# Snake.net
KiCad netlist of a schematic drawn in EAGLE
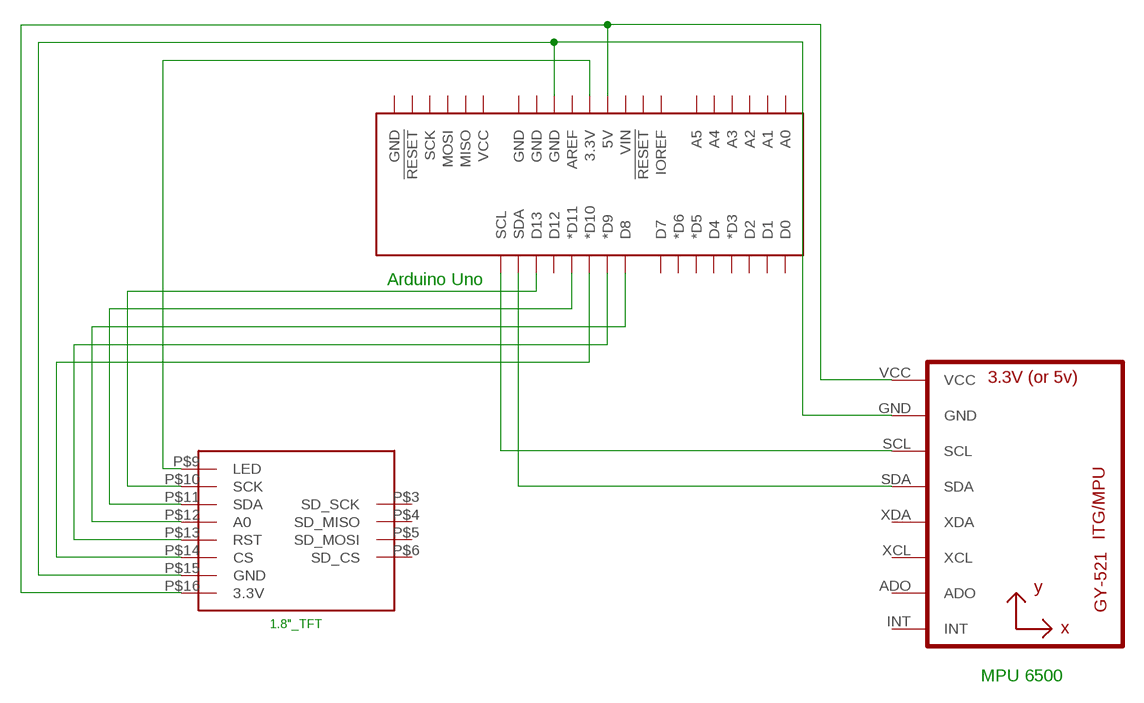
[diagram p0: schematic, sheet 1]

(export (version "E")
  (design (tool "Eeschema 10.0.6"))
  (components
    (comp (ref "B1")
      (value "ARDUINO_UNO_R3NO_HOLES")
      (footprint "eagle-import:ARDUINO_R3_NO_HOLES")
      (libsource (lib "eagle-import") (part "ARDUINO_UNO_R3NO_HOLES"))
    )
    (comp (ref "U$1")
      (value "1.8\"_TFT")
      (footprint "eagle-import:1.8__TFT")
      (libsource (lib "eagle-import") (part "1.8{dblquote}_TFT"))
    )
    (comp (ref "U1")
      (value "GY-521MPU6050")
      (footprint "eagle-import:GY-521")
      (libsource (lib "eagle-import") (part "GY-521MPU6050"))
    )
  )
  (nets
    (net (code "1") (name "Net-(B1-*D9)") (class "Default")
      (node (ref "B1") (pin "D9") (pinfunction "*D9_D9") (pintype "bidirectional"))
      (node (ref "U$1") (pin "P$13") (pinfunction "RST_P$13") (pintype "bidirectional"))
    )
    (net (code "2") (name "Net-(B1-*D10)") (class "Default")
      (node (ref "B1") (pin "D10") (pinfunction "*D10_D10") (pintype "bidirectional"))
      (node (ref "U$1") (pin "P$14") (pinfunction "CS_P$14") (pintype "bidirectional"))
    )
    (net (code "3") (name "Net-(B1-*D11)") (class "Default")
      (node (ref "B1") (pin "D11") (pinfunction "*D11_D11") (pintype "bidirectional"))
      (node (ref "U$1") (pin "P$11") (pinfunction "SDA_P$11") (pintype "bidirectional"))
    )
    (net (code "4") (name "Net-(B1-PadSCL)") (class "Default")
      (node (ref "B1") (pin "SCL") (pinfunction "SCL_SCL") (pintype "bidirectional"))
      (node (ref "U1") (pin "SCL") (pinfunction "SCL_SCL") (pintype "bidirectional"))
    )
    (net (code "5") (name "Net-(B1-PadSDA)") (class "Default")
      (node (ref "B1") (pin "SDA") (pinfunction "SDA_SDA") (pintype "bidirectional"))
      (node (ref "U1") (pin "SDA") (pinfunction "SDA_SDA") (pintype "bidirectional"))
    )
    (net (code "6") (name "Net-(U$1-3.3V)") (class "Default")
      (node (ref "B1") (pin "5V") (pinfunction "5V_5V") (pintype "bidirectional"))
      (node (ref "U$1") (pin "P$16") (pinfunction "3.3V_P$16") (pintype "bidirectional"))
      (node (ref "U1") (pin "VCC") (pinfunction "VCC_VCC") (pintype "bidirectional"))
    )
    (net (code "7") (name "Net-(U$1-A0)") (class "Default")
      (node (ref "B1") (pin "D8") (pinfunction "D8_D8") (pintype "bidirectional"))
      (node (ref "U$1") (pin "P$12") (pinfunction "A0_P$12") (pintype "bidirectional"))
    )
    (net (code "8") (name "Net-(U$1-GND)") (class "Default")
      (node (ref "B1") (pin "GND@4") (pinfunction "GND_GND@4") (pintype "bidirectional"))
      (node (ref "U$1") (pin "P$15") (pinfunction "GND_P$15") (pintype "bidirectional"))
      (node (ref "U1") (pin "GND") (pinfunction "GND_GND") (pintype "bidirectional"))
    )
    (net (code "9") (name "Net-(U$1-LED)") (class "Default")
      (node (ref "B1") (pin "3.3V") (pinfunction "3.3V_3.3V") (pintype "bidirectional"))
      (node (ref "U$1") (pin "P$9") (pinfunction "LED_P$9") (pintype "bidirectional"))
    )
    (net (code "10") (name "Net-(U$1-SCK)") (class "Default")
      (node (ref "B1") (pin "D13") (pinfunction "D13_D13") (pintype "bidirectional"))
      (node (ref "U$1") (pin "P$10") (pinfunction "SCK_P$10") (pintype "bidirectional"))
    )
    (net (code "11") (name "unconnected-(B1-*D3-PadD3)") (class "Default")
      (node (ref "B1") (pin "D3") (pinfunction "*D3_D3") (pintype "bidirectional"))
    )
    (net (code "12") (name "unconnected-(B1-*D5-PadD5)") (class "Default")
      (node (ref "B1") (pin "D5") (pinfunction "*D5_D5") (pintype "bidirectional"))
    )
    (net (code "13") (name "unconnected-(B1-*D6-PadD6)") (class "Default")
      (node (ref "B1") (pin "D6") (pinfunction "*D6_D6") (pintype "bidirectional"))
    )
    (net (code "14") (name "unconnected-(B1-GND-PadGND@1)") (class "Default")
      (node (ref "B1") (pin "GND@1") (pinfunction "GND_GND@1") (pintype "bidirectional"))
    )
    (net (code "15") (name "unconnected-(B1-GND-PadGND@2)") (class "Default")
      (node (ref "B1") (pin "GND@2") (pinfunction "GND_GND@2") (pintype "bidirectional"))
    )
    (net (code "16") (name "unconnected-(B1-GND-PadGND@3)") (class "Default")
      (node (ref "B1") (pin "GND@3") (pinfunction "GND_GND@3") (pintype "bidirectional"))
    )
    (net (code "17") (name "unconnected-(B1-PadA0)") (class "Default")
      (node (ref "B1") (pin "A0") (pinfunction "A0_A0") (pintype "bidirectional"))
    )
    (net (code "18") (name "unconnected-(B1-PadA1)") (class "Default")
      (node (ref "B1") (pin "A1") (pinfunction "A1_A1") (pintype "bidirectional"))
    )
    (net (code "19") (name "unconnected-(B1-PadA2)") (class "Default")
      (node (ref "B1") (pin "A2") (pinfunction "A2_A2") (pintype "bidirectional"))
    )
    (net (code "20") (name "unconnected-(B1-PadA3)") (class "Default")
      (node (ref "B1") (pin "A3") (pinfunction "A3_A3") (pintype "bidirectional"))
    )
    (net (code "21") (name "unconnected-(B1-PadA4)") (class "Default")
      (node (ref "B1") (pin "A4") (pinfunction "A4_A4") (pintype "bidirectional"))
    )
    (net (code "22") (name "unconnected-(B1-PadA5)") (class "Default")
      (node (ref "B1") (pin "A5") (pinfunction "A5_A5") (pintype "bidirectional"))
    )
    (net (code "23") (name "unconnected-(B1-PadAREF)") (class "Default")
      (node (ref "B1") (pin "AREF") (pinfunction "AREF_AREF") (pintype "bidirectional"))
    )
    (net (code "24") (name "unconnected-(B1-PadD0)") (class "Default")
      (node (ref "B1") (pin "D0") (pinfunction "D0_D0") (pintype "bidirectional"))
    )
    (net (code "25") (name "unconnected-(B1-PadD1)") (class "Default")
      (node (ref "B1") (pin "D1") (pinfunction "D1_D1") (pintype "bidirectional"))
    )
    (net (code "26") (name "unconnected-(B1-PadD2)") (class "Default")
      (node (ref "B1") (pin "D2") (pinfunction "D2_D2") (pintype "bidirectional"))
    )
    (net (code "27") (name "unconnected-(B1-PadD4)") (class "Default")
      (node (ref "B1") (pin "D4") (pinfunction "D4_D4") (pintype "bidirectional"))
    )
    (net (code "28") (name "unconnected-(B1-PadD7)") (class "Default")
      (node (ref "B1") (pin "D7") (pinfunction "D7_D7") (pintype "bidirectional"))
    )
    (net (code "29") (name "unconnected-(B1-PadD12)") (class "Default")
      (node (ref "B1") (pin "D12") (pinfunction "D12_D12") (pintype "bidirectional"))
    )
    (net (code "30") (name "unconnected-(B1-PadIOREF)") (class "Default")
      (node (ref "B1") (pin "IOREF") (pinfunction "IOREF_IOREF") (pintype "bidirectional"))
    )
    (net (code "31") (name "unconnected-(B1-PadMISO)") (class "Default")
      (node (ref "B1") (pin "MISO") (pinfunction "MISO_MISO") (pintype "bidirectional"))
    )
    (net (code "32") (name "unconnected-(B1-PadMOSI)") (class "Default")
      (node (ref "B1") (pin "MOSI") (pinfunction "MOSI_MOSI") (pintype "bidirectional"))
    )
    (net (code "33") (name "unconnected-(B1-PadSCK)") (class "Default")
      (node (ref "B1") (pin "SCK") (pinfunction "SCK_SCK") (pintype "bidirectional"))
    )
    (net (code "34") (name "unconnected-(B1-PadVCC)") (class "Default")
      (node (ref "B1") (pin "VCC") (pinfunction "VCC_VCC") (pintype "bidirectional"))
    )
    (net (code "35") (name "unconnected-(B1-PadVIN)") (class "Default")
      (node (ref "B1") (pin "VIN") (pinfunction "VIN_VIN") (pintype "bidirectional"))
    )
    (net (code "36") (name "unconnected-(B1-~{RESET}-PadRESET@1)") (class "Default")
      (node (ref "B1") (pin "RESET@1") (pinfunction "~{RESET}_RESET@1") (pintype "bidirectional"))
    )
    (net (code "37") (name "unconnected-(B1-~{RESET}-PadRESET@2)") (class "Default")
      (node (ref "B1") (pin "RESET@2") (pinfunction "~{RESET}_RESET@2") (pintype "bidirectional"))
    )
    (net (code "38") (name "unconnected-(U$1-SD_CS-PadP$6)") (class "Default")
      (node (ref "U$1") (pin "P$6") (pinfunction "SD_CS_P$6") (pintype "bidirectional"))
    )
    (net (code "39") (name "unconnected-(U$1-SD_MISO-PadP$4)") (class "Default")
      (node (ref "U$1") (pin "P$4") (pinfunction "SD_MISO_P$4") (pintype "bidirectional"))
    )
    (net (code "40") (name "unconnected-(U$1-SD_MOSI-PadP$5)") (class "Default")
      (node (ref "U$1") (pin "P$5") (pinfunction "SD_MOSI_P$5") (pintype "bidirectional"))
    )
    (net (code "41") (name "unconnected-(U$1-SD_SCK-PadP$3)") (class "Default")
      (node (ref "U$1") (pin "P$3") (pinfunction "SD_SCK_P$3") (pintype "bidirectional"))
    )
    (net (code "42") (name "unconnected-(U1-PadADO)") (class "Default")
      (node (ref "U1") (pin "ADO") (pinfunction "ADO_ADO") (pintype "bidirectional"))
    )
    (net (code "43") (name "unconnected-(U1-PadINT)") (class "Default")
      (node (ref "U1") (pin "INT") (pinfunction "INT_INT") (pintype "bidirectional"))
    )
    (net (code "44") (name "unconnected-(U1-PadXCL)") (class "Default")
      (node (ref "U1") (pin "XCL") (pinfunction "XCL_XCL") (pintype "bidirectional"))
    )
    (net (code "45") (name "unconnected-(U1-PadXDA)") (class "Default")
      (node (ref "U1") (pin "XDA") (pinfunction "XDA_XDA") (pintype "bidirectional"))
    )
  )
)
